# Rev1.net
KiCad netlist of a schematic drawn in EAGLE
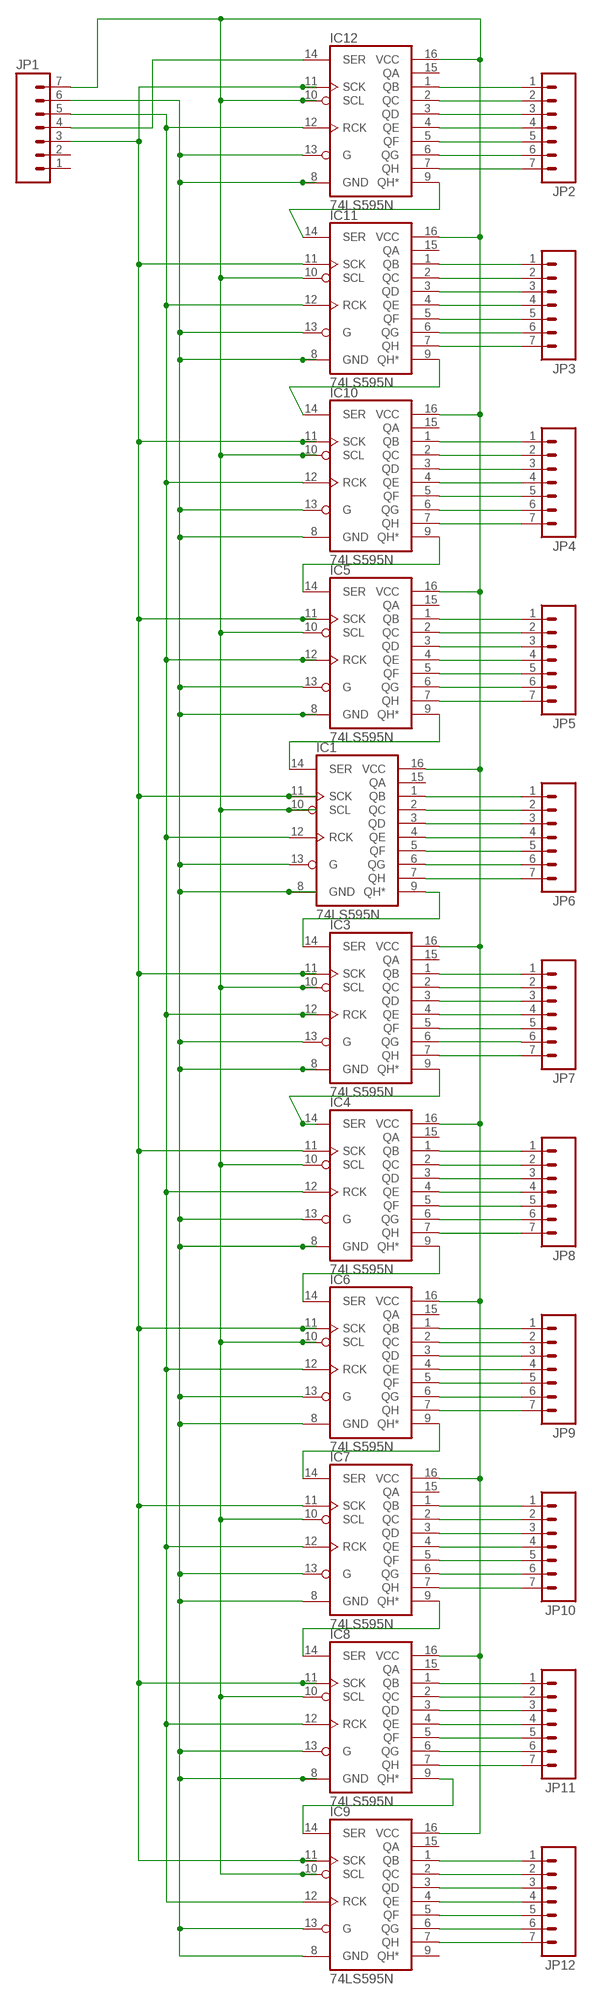
[diagram p0: schematic, sheet 1]

(export (version "E")
  (design (tool "Eeschema 10.0.6"))
  (components
    (comp (ref "IC1")
      (value "74LS595N")
      (footprint "eagle-import:DIL16")
      (libsource (lib "eagle-import") (part "74595NLS"))
    )
    (comp (ref "IC3")
      (value "74LS595N")
      (footprint "eagle-import:DIL16")
      (libsource (lib "eagle-import") (part "74595NLS"))
    )
    (comp (ref "IC4")
      (value "74LS595N")
      (footprint "eagle-import:DIL16")
      (libsource (lib "eagle-import") (part "74595NLS"))
    )
    (comp (ref "IC5")
      (value "74LS595N")
      (footprint "eagle-import:DIL16")
      (libsource (lib "eagle-import") (part "74595NLS"))
    )
    (comp (ref "IC6")
      (value "74LS595N")
      (footprint "eagle-import:DIL16")
      (libsource (lib "eagle-import") (part "74595NLS"))
    )
    (comp (ref "IC7")
      (value "74LS595N")
      (footprint "eagle-import:DIL16")
      (libsource (lib "eagle-import") (part "74595NLS"))
    )
    (comp (ref "IC8")
      (value "74LS595N")
      (footprint "eagle-import:DIL16")
      (libsource (lib "eagle-import") (part "74595NLS"))
    )
    (comp (ref "IC9")
      (value "74LS595N")
      (footprint "eagle-import:DIL16")
      (libsource (lib "eagle-import") (part "74595NLS"))
    )
    (comp (ref "IC10")
      (value "74LS595N")
      (footprint "eagle-import:DIL16")
      (libsource (lib "eagle-import") (part "74595NLS"))
    )
    (comp (ref "IC11")
      (value "74LS595N")
      (footprint "eagle-import:DIL16")
      (libsource (lib "eagle-import") (part "74595NLS"))
    )
    (comp (ref "IC12")
      (value "74LS595N")
      (footprint "eagle-import:DIL16")
      (libsource (lib "eagle-import") (part "74595NLS"))
    )
    (comp (ref "JP1")
      (value "M07")
      (footprint "eagle-import:1X07")
      (libsource (lib "eagle-import") (part "M07"))
    )
    (comp (ref "JP2")
      (value "M07")
      (footprint "eagle-import:1X07")
      (libsource (lib "eagle-import") (part "M07"))
    )
    (comp (ref "JP3")
      (value "M07")
      (footprint "eagle-import:1X07")
      (libsource (lib "eagle-import") (part "M07"))
    )
    (comp (ref "JP4")
      (value "M07")
      (footprint "eagle-import:1X07")
      (libsource (lib "eagle-import") (part "M07"))
    )
    (comp (ref "JP5")
      (value "M07")
      (footprint "eagle-import:1X07")
      (libsource (lib "eagle-import") (part "M07"))
    )
    (comp (ref "JP6")
      (value "M07")
      (footprint "eagle-import:1X07")
      (libsource (lib "eagle-import") (part "M07"))
    )
    (comp (ref "JP7")
      (value "M07")
      (footprint "eagle-import:1X07")
      (libsource (lib "eagle-import") (part "M07"))
    )
    (comp (ref "JP8")
      (value "M07")
      (footprint "eagle-import:1X07")
      (libsource (lib "eagle-import") (part "M07"))
    )
    (comp (ref "JP9")
      (value "M07")
      (footprint "eagle-import:1X07")
      (libsource (lib "eagle-import") (part "M07"))
    )
    (comp (ref "JP10")
      (value "M07")
      (footprint "eagle-import:1X07")
      (libsource (lib "eagle-import") (part "M07"))
    )
    (comp (ref "JP11")
      (value "M07")
      (footprint "eagle-import:1X07")
      (libsource (lib "eagle-import") (part "M07"))
    )
    (comp (ref "JP12")
      (value "M07")
      (footprint "eagle-import:1X07")
      (libsource (lib "eagle-import") (part "M07"))
    )
  )
  (nets
    (net (code "1") (name "Net-(IC1-G)") (class "Default")
      (node (ref "IC1") (pin "13") (pinfunction "G_13") (pintype "input"))
      (node (ref "IC1") (pin "8") (pinfunction "GND_8") (pintype "power_in"))
      (node (ref "IC10") (pin "13") (pinfunction "G_13") (pintype "input"))
      (node (ref "IC10") (pin "8") (pinfunction "GND_8") (pintype "power_in"))
      (node (ref "IC11") (pin "13") (pinfunction "G_13") (pintype "input"))
      (node (ref "IC11") (pin "8") (pinfunction "GND_8") (pintype "power_in"))
      (node (ref "IC12") (pin "13") (pinfunction "G_13") (pintype "input"))
      (node (ref "IC12") (pin "8") (pinfunction "GND_8") (pintype "power_in"))
      (node (ref "IC3") (pin "13") (pinfunction "G_13") (pintype "input"))
      (node (ref "IC3") (pin "8") (pinfunction "GND_8") (pintype "power_in"))
      (node (ref "IC4") (pin "13") (pinfunction "G_13") (pintype "input"))
      (node (ref "IC4") (pin "8") (pinfunction "GND_8") (pintype "power_in"))
      (node (ref "IC5") (pin "13") (pinfunction "G_13") (pintype "input"))
      (node (ref "IC5") (pin "8") (pinfunction "GND_8") (pintype "power_in"))
      (node (ref "IC6") (pin "13") (pinfunction "G_13") (pintype "input"))
      (node (ref "IC6") (pin "8") (pinfunction "GND_8") (pintype "power_in"))
      (node (ref "IC7") (pin "13") (pinfunction "G_13") (pintype "input"))
      (node (ref "IC7") (pin "8") (pinfunction "GND_8") (pintype "power_in"))
      (node (ref "IC8") (pin "13") (pinfunction "G_13") (pintype "input"))
      (node (ref "IC8") (pin "8") (pinfunction "GND_8") (pintype "power_in"))
      (node (ref "IC9") (pin "13") (pinfunction "G_13") (pintype "input"))
      (node (ref "IC9") (pin "8") (pinfunction "GND_8") (pintype "power_in"))
      (node (ref "JP1") (pin "6") (pinfunction "6_6") (pintype "passive"))
    )
    (net (code "2") (name "Net-(IC1-QB)") (class "Default")
      (node (ref "IC1") (pin "1") (pinfunction "QB_1") (pintype "tri_state"))
      (node (ref "JP6") (pin "1") (pinfunction "1_1") (pintype "passive"))
    )
    (net (code "3") (name "Net-(IC1-QC)") (class "Default")
      (node (ref "IC1") (pin "2") (pinfunction "QC_2") (pintype "tri_state"))
      (node (ref "JP6") (pin "2") (pinfunction "2_2") (pintype "passive"))
    )
    (net (code "4") (name "Net-(IC1-QD)") (class "Default")
      (node (ref "IC1") (pin "3") (pinfunction "QD_3") (pintype "tri_state"))
      (node (ref "JP6") (pin "3") (pinfunction "3_3") (pintype "passive"))
    )
    (net (code "5") (name "Net-(IC1-QE)") (class "Default")
      (node (ref "IC1") (pin "4") (pinfunction "QE_4") (pintype "tri_state"))
      (node (ref "JP6") (pin "4") (pinfunction "4_4") (pintype "passive"))
    )
    (net (code "6") (name "Net-(IC1-QF)") (class "Default")
      (node (ref "IC1") (pin "5") (pinfunction "QF_5") (pintype "tri_state"))
      (node (ref "JP6") (pin "5") (pinfunction "5_5") (pintype "passive"))
    )
    (net (code "7") (name "Net-(IC1-QG)") (class "Default")
      (node (ref "IC1") (pin "6") (pinfunction "QG_6") (pintype "tri_state"))
      (node (ref "JP6") (pin "6") (pinfunction "6_6") (pintype "passive"))
    )
    (net (code "8") (name "Net-(IC1-QH)") (class "Default")
      (node (ref "IC1") (pin "7") (pinfunction "QH_7") (pintype "tri_state"))
      (node (ref "JP6") (pin "7") (pinfunction "7_7") (pintype "passive"))
    )
    (net (code "9") (name "Net-(IC1-QH*)") (class "Default")
      (node (ref "IC1") (pin "9") (pinfunction "QH*_9") (pintype "tri_state"))
      (node (ref "IC3") (pin "14") (pinfunction "SER_14") (pintype "input"))
    )
    (net (code "10") (name "Net-(IC1-RCK)") (class "Default")
      (node (ref "IC1") (pin "12") (pinfunction "RCK_12") (pintype "input"))
      (node (ref "IC10") (pin "12") (pinfunction "RCK_12") (pintype "input"))
      (node (ref "IC11") (pin "12") (pinfunction "RCK_12") (pintype "input"))
      (node (ref "IC12") (pin "12") (pinfunction "RCK_12") (pintype "input"))
      (node (ref "IC3") (pin "12") (pinfunction "RCK_12") (pintype "input"))
      (node (ref "IC4") (pin "12") (pinfunction "RCK_12") (pintype "input"))
      (node (ref "IC5") (pin "12") (pinfunction "RCK_12") (pintype "input"))
      (node (ref "IC6") (pin "12") (pinfunction "RCK_12") (pintype "input"))
      (node (ref "IC7") (pin "12") (pinfunction "RCK_12") (pintype "input"))
      (node (ref "IC8") (pin "12") (pinfunction "RCK_12") (pintype "input"))
      (node (ref "IC9") (pin "12") (pinfunction "RCK_12") (pintype "input"))
      (node (ref "JP1") (pin "5") (pinfunction "5_5") (pintype "passive"))
    )
    (net (code "11") (name "Net-(IC1-SCK)") (class "Default")
      (node (ref "IC1") (pin "11") (pinfunction "SCK_11") (pintype "input"))
      (node (ref "IC10") (pin "11") (pinfunction "SCK_11") (pintype "input"))
      (node (ref "IC11") (pin "11") (pinfunction "SCK_11") (pintype "input"))
      (node (ref "IC12") (pin "11") (pinfunction "SCK_11") (pintype "input"))
      (node (ref "IC3") (pin "11") (pinfunction "SCK_11") (pintype "input"))
      (node (ref "IC4") (pin "11") (pinfunction "SCK_11") (pintype "input"))
      (node (ref "IC5") (pin "11") (pinfunction "SCK_11") (pintype "input"))
      (node (ref "IC6") (pin "11") (pinfunction "SCK_11") (pintype "input"))
      (node (ref "IC7") (pin "11") (pinfunction "SCK_11") (pintype "input"))
      (node (ref "IC8") (pin "11") (pinfunction "SCK_11") (pintype "input"))
      (node (ref "IC9") (pin "11") (pinfunction "SCK_11") (pintype "input"))
      (node (ref "JP1") (pin "3") (pinfunction "3_3") (pintype "passive"))
    )
    (net (code "12") (name "Net-(IC1-SCL)") (class "Default")
      (node (ref "IC1") (pin "10") (pinfunction "SCL_10") (pintype "input"))
      (node (ref "IC1") (pin "16") (pinfunction "VCC_16") (pintype "power_in"))
      (node (ref "IC10") (pin "10") (pinfunction "SCL_10") (pintype "input"))
      (node (ref "IC10") (pin "16") (pinfunction "VCC_16") (pintype "power_in"))
      (node (ref "IC11") (pin "10") (pinfunction "SCL_10") (pintype "input"))
      (node (ref "IC11") (pin "16") (pinfunction "VCC_16") (pintype "power_in"))
      (node (ref "IC12") (pin "10") (pinfunction "SCL_10") (pintype "input"))
      (node (ref "IC12") (pin "16") (pinfunction "VCC_16") (pintype "power_in"))
      (node (ref "IC3") (pin "10") (pinfunction "SCL_10") (pintype "input"))
      (node (ref "IC3") (pin "16") (pinfunction "VCC_16") (pintype "power_in"))
      (node (ref "IC4") (pin "10") (pinfunction "SCL_10") (pintype "input"))
      (node (ref "IC4") (pin "16") (pinfunction "VCC_16") (pintype "power_in"))
      (node (ref "IC5") (pin "10") (pinfunction "SCL_10") (pintype "input"))
      (node (ref "IC5") (pin "16") (pinfunction "VCC_16") (pintype "power_in"))
      (node (ref "IC6") (pin "10") (pinfunction "SCL_10") (pintype "input"))
      (node (ref "IC6") (pin "16") (pinfunction "VCC_16") (pintype "power_in"))
      (node (ref "IC7") (pin "10") (pinfunction "SCL_10") (pintype "input"))
      (node (ref "IC7") (pin "16") (pinfunction "VCC_16") (pintype "power_in"))
      (node (ref "IC8") (pin "10") (pinfunction "SCL_10") (pintype "input"))
      (node (ref "IC8") (pin "16") (pinfunction "VCC_16") (pintype "power_in"))
      (node (ref "IC9") (pin "10") (pinfunction "SCL_10") (pintype "input"))
      (node (ref "IC9") (pin "16") (pinfunction "VCC_16") (pintype "power_in"))
      (node (ref "JP1") (pin "7") (pinfunction "7_7") (pintype "passive"))
    )
    (net (code "13") (name "Net-(IC1-SER)") (class "Default")
      (node (ref "IC1") (pin "14") (pinfunction "SER_14") (pintype "input"))
      (node (ref "IC5") (pin "9") (pinfunction "QH*_9") (pintype "tri_state"))
    )
    (net (code "14") (name "Net-(IC3-QB)") (class "Default")
      (node (ref "IC3") (pin "1") (pinfunction "QB_1") (pintype "tri_state"))
      (node (ref "JP7") (pin "1") (pinfunction "1_1") (pintype "passive"))
    )
    (net (code "15") (name "Net-(IC3-QC)") (class "Default")
      (node (ref "IC3") (pin "2") (pinfunction "QC_2") (pintype "tri_state"))
      (node (ref "JP7") (pin "2") (pinfunction "2_2") (pintype "passive"))
    )
    (net (code "16") (name "Net-(IC3-QD)") (class "Default")
      (node (ref "IC3") (pin "3") (pinfunction "QD_3") (pintype "tri_state"))
      (node (ref "JP7") (pin "3") (pinfunction "3_3") (pintype "passive"))
    )
    (net (code "17") (name "Net-(IC3-QE)") (class "Default")
      (node (ref "IC3") (pin "4") (pinfunction "QE_4") (pintype "tri_state"))
      (node (ref "JP7") (pin "4") (pinfunction "4_4") (pintype "passive"))
    )
    (net (code "18") (name "Net-(IC3-QF)") (class "Default")
      (node (ref "IC3") (pin "5") (pinfunction "QF_5") (pintype "tri_state"))
      (node (ref "JP7") (pin "5") (pinfunction "5_5") (pintype "passive"))
    )
    (net (code "19") (name "Net-(IC3-QG)") (class "Default")
      (node (ref "IC3") (pin "6") (pinfunction "QG_6") (pintype "tri_state"))
      (node (ref "JP7") (pin "6") (pinfunction "6_6") (pintype "passive"))
    )
    (net (code "20") (name "Net-(IC3-QH)") (class "Default")
      (node (ref "IC3") (pin "7") (pinfunction "QH_7") (pintype "tri_state"))
      (node (ref "JP7") (pin "7") (pinfunction "7_7") (pintype "passive"))
    )
    (net (code "21") (name "Net-(IC3-QH*)") (class "Default")
      (node (ref "IC3") (pin "9") (pinfunction "QH*_9") (pintype "tri_state"))
      (node (ref "IC4") (pin "14") (pinfunction "SER_14") (pintype "input"))
    )
    (net (code "22") (name "Net-(IC4-QB)") (class "Default")
      (node (ref "IC4") (pin "1") (pinfunction "QB_1") (pintype "tri_state"))
      (node (ref "JP8") (pin "1") (pinfunction "1_1") (pintype "passive"))
    )
    (net (code "23") (name "Net-(IC4-QC)") (class "Default")
      (node (ref "IC4") (pin "2") (pinfunction "QC_2") (pintype "tri_state"))
      (node (ref "JP8") (pin "2") (pinfunction "2_2") (pintype "passive"))
    )
    (net (code "24") (name "Net-(IC4-QD)") (class "Default")
      (node (ref "IC4") (pin "3") (pinfunction "QD_3") (pintype "tri_state"))
      (node (ref "JP8") (pin "3") (pinfunction "3_3") (pintype "passive"))
    )
    (net (code "25") (name "Net-(IC4-QE)") (class "Default")
      (node (ref "IC4") (pin "4") (pinfunction "QE_4") (pintype "tri_state"))
      (node (ref "JP8") (pin "4") (pinfunction "4_4") (pintype "passive"))
    )
    (net (code "26") (name "Net-(IC4-QF)") (class "Default")
      (node (ref "IC4") (pin "5") (pinfunction "QF_5") (pintype "tri_state"))
      (node (ref "JP8") (pin "5") (pinfunction "5_5") (pintype "passive"))
    )
    (net (code "27") (name "Net-(IC4-QG)") (class "Default")
      (node (ref "IC4") (pin "6") (pinfunction "QG_6") (pintype "tri_state"))
      (node (ref "JP8") (pin "6") (pinfunction "6_6") (pintype "passive"))
    )
    (net (code "28") (name "Net-(IC4-QH)") (class "Default")
      (node (ref "IC4") (pin "7") (pinfunction "QH_7") (pintype "tri_state"))
      (node (ref "JP8") (pin "7") (pinfunction "7_7") (pintype "passive"))
    )
    (net (code "29") (name "Net-(IC4-QH*)") (class "Default")
      (node (ref "IC4") (pin "9") (pinfunction "QH*_9") (pintype "tri_state"))
      (node (ref "IC6") (pin "14") (pinfunction "SER_14") (pintype "input"))
    )
    (net (code "30") (name "Net-(IC5-QB)") (class "Default")
      (node (ref "IC5") (pin "1") (pinfunction "QB_1") (pintype "tri_state"))
      (node (ref "JP5") (pin "1") (pinfunction "1_1") (pintype "passive"))
    )
    (net (code "31") (name "Net-(IC5-QC)") (class "Default")
      (node (ref "IC5") (pin "2") (pinfunction "QC_2") (pintype "tri_state"))
      (node (ref "JP5") (pin "2") (pinfunction "2_2") (pintype "passive"))
    )
    (net (code "32") (name "Net-(IC5-QD)") (class "Default")
      (node (ref "IC5") (pin "3") (pinfunction "QD_3") (pintype "tri_state"))
      (node (ref "JP5") (pin "3") (pinfunction "3_3") (pintype "passive"))
    )
    (net (code "33") (name "Net-(IC5-QE)") (class "Default")
      (node (ref "IC5") (pin "4") (pinfunction "QE_4") (pintype "tri_state"))
      (node (ref "JP5") (pin "4") (pinfunction "4_4") (pintype "passive"))
    )
    (net (code "34") (name "Net-(IC5-QF)") (class "Default")
      (node (ref "IC5") (pin "5") (pinfunction "QF_5") (pintype "tri_state"))
      (node (ref "JP5") (pin "5") (pinfunction "5_5") (pintype "passive"))
    )
    (net (code "35") (name "Net-(IC5-QG)") (class "Default")
      (node (ref "IC5") (pin "6") (pinfunction "QG_6") (pintype "tri_state"))
      (node (ref "JP5") (pin "6") (pinfunction "6_6") (pintype "passive"))
    )
    (net (code "36") (name "Net-(IC5-QH)") (class "Default")
      (node (ref "IC5") (pin "7") (pinfunction "QH_7") (pintype "tri_state"))
      (node (ref "JP5") (pin "7") (pinfunction "7_7") (pintype "passive"))
    )
    (net (code "37") (name "Net-(IC6-QB)") (class "Default")
      (node (ref "IC6") (pin "1") (pinfunction "QB_1") (pintype "tri_state"))
      (node (ref "JP9") (pin "1") (pinfunction "1_1") (pintype "passive"))
    )
    (net (code "38") (name "Net-(IC6-QC)") (class "Default")
      (node (ref "IC6") (pin "2") (pinfunction "QC_2") (pintype "tri_state"))
      (node (ref "JP9") (pin "2") (pinfunction "2_2") (pintype "passive"))
    )
    (net (code "39") (name "Net-(IC6-QD)") (class "Default")
      (node (ref "IC6") (pin "3") (pinfunction "QD_3") (pintype "tri_state"))
      (node (ref "JP9") (pin "3") (pinfunction "3_3") (pintype "passive"))
    )
    (net (code "40") (name "Net-(IC6-QE)") (class "Default")
      (node (ref "IC6") (pin "4") (pinfunction "QE_4") (pintype "tri_state"))
      (node (ref "JP9") (pin "4") (pinfunction "4_4") (pintype "passive"))
    )
    (net (code "41") (name "Net-(IC6-QF)") (class "Default")
      (node (ref "IC6") (pin "5") (pinfunction "QF_5") (pintype "tri_state"))
      (node (ref "JP9") (pin "5") (pinfunction "5_5") (pintype "passive"))
    )
    (net (code "42") (name "Net-(IC6-QG)") (class "Default")
      (node (ref "IC6") (pin "6") (pinfunction "QG_6") (pintype "tri_state"))
      (node (ref "JP9") (pin "6") (pinfunction "6_6") (pintype "passive"))
    )
    (net (code "43") (name "Net-(IC6-QH)") (class "Default")
      (node (ref "IC6") (pin "7") (pinfunction "QH_7") (pintype "tri_state"))
      (node (ref "JP9") (pin "7") (pinfunction "7_7") (pintype "passive"))
    )
    (net (code "44") (name "Net-(IC6-QH*)") (class "Default")
      (node (ref "IC6") (pin "9") (pinfunction "QH*_9") (pintype "tri_state"))
      (node (ref "IC7") (pin "14") (pinfunction "SER_14") (pintype "input"))
    )
    (net (code "45") (name "Net-(IC7-QB)") (class "Default")
      (node (ref "IC7") (pin "1") (pinfunction "QB_1") (pintype "tri_state"))
      (node (ref "JP10") (pin "1") (pinfunction "1_1") (pintype "passive"))
    )
    (net (code "46") (name "Net-(IC7-QC)") (class "Default")
      (node (ref "IC7") (pin "2") (pinfunction "QC_2") (pintype "tri_state"))
      (node (ref "JP10") (pin "2") (pinfunction "2_2") (pintype "passive"))
    )
    (net (code "47") (name "Net-(IC7-QD)") (class "Default")
      (node (ref "IC7") (pin "3") (pinfunction "QD_3") (pintype "tri_state"))
      (node (ref "JP10") (pin "3") (pinfunction "3_3") (pintype "passive"))
    )
    (net (code "48") (name "Net-(IC7-QE)") (class "Default")
      (node (ref "IC7") (pin "4") (pinfunction "QE_4") (pintype "tri_state"))
      (node (ref "JP10") (pin "4") (pinfunction "4_4") (pintype "passive"))
    )
    (net (code "49") (name "Net-(IC7-QF)") (class "Default")
      (node (ref "IC7") (pin "5") (pinfunction "QF_5") (pintype "tri_state"))
      (node (ref "JP10") (pin "5") (pinfunction "5_5") (pintype "passive"))
    )
    (net (code "50") (name "Net-(IC7-QG)") (class "Default")
      (node (ref "IC7") (pin "6") (pinfunction "QG_6") (pintype "tri_state"))
      (node (ref "JP10") (pin "6") (pinfunction "6_6") (pintype "passive"))
    )
    (net (code "51") (name "Net-(IC7-QH)") (class "Default")
      (node (ref "IC7") (pin "7") (pinfunction "QH_7") (pintype "tri_state"))
      (node (ref "JP10") (pin "7") (pinfunction "7_7") (pintype "passive"))
    )
    (net (code "52") (name "Net-(IC7-QH*)") (class "Default")
      (node (ref "IC7") (pin "9") (pinfunction "QH*_9") (pintype "tri_state"))
      (node (ref "IC8") (pin "14") (pinfunction "SER_14") (pintype "input"))
    )
    (net (code "53") (name "Net-(IC8-QB)") (class "Default")
      (node (ref "IC8") (pin "1") (pinfunction "QB_1") (pintype "tri_state"))
      (node (ref "JP11") (pin "1") (pinfunction "1_1") (pintype "passive"))
    )
    (net (code "54") (name "Net-(IC8-QC)") (class "Default")
      (node (ref "IC8") (pin "2") (pinfunction "QC_2") (pintype "tri_state"))
      (node (ref "JP11") (pin "2") (pinfunction "2_2") (pintype "passive"))
    )
    (net (code "55") (name "Net-(IC8-QD)") (class "Default")
      (node (ref "IC8") (pin "3") (pinfunction "QD_3") (pintype "tri_state"))
      (node (ref "JP11") (pin "3") (pinfunction "3_3") (pintype "passive"))
    )
    (net (code "56") (name "Net-(IC8-QE)") (class "Default")
      (node (ref "IC8") (pin "4") (pinfunction "QE_4") (pintype "tri_state"))
      (node (ref "JP11") (pin "4") (pinfunction "4_4") (pintype "passive"))
    )
    (net (code "57") (name "Net-(IC8-QF)") (class "Default")
      (node (ref "IC8") (pin "5") (pinfunction "QF_5") (pintype "tri_state"))
      (node (ref "JP11") (pin "5") (pinfunction "5_5") (pintype "passive"))
    )
    (net (code "58") (name "Net-(IC8-QG)") (class "Default")
      (node (ref "IC8") (pin "6") (pinfunction "QG_6") (pintype "tri_state"))
      (node (ref "JP11") (pin "6") (pinfunction "6_6") (pintype "passive"))
    )
    (net (code "59") (name "Net-(IC8-QH)") (class "Default")
      (node (ref "IC8") (pin "7") (pinfunction "QH_7") (pintype "tri_state"))
      (node (ref "JP11") (pin "7") (pinfunction "7_7") (pintype "passive"))
    )
    (net (code "60") (name "Net-(IC8-QH*)") (class "Default")
      (node (ref "IC8") (pin "9") (pinfunction "QH*_9") (pintype "tri_state"))
      (node (ref "IC9") (pin "14") (pinfunction "SER_14") (pintype "input"))
    )
    (net (code "61") (name "Net-(IC9-QB)") (class "Default")
      (node (ref "IC9") (pin "1") (pinfunction "QB_1") (pintype "tri_state"))
      (node (ref "JP12") (pin "1") (pinfunction "1_1") (pintype "passive"))
    )
    (net (code "62") (name "Net-(IC9-QC)") (class "Default")
      (node (ref "IC9") (pin "2") (pinfunction "QC_2") (pintype "tri_state"))
      (node (ref "JP12") (pin "2") (pinfunction "2_2") (pintype "passive"))
    )
    (net (code "63") (name "Net-(IC9-QD)") (class "Default")
      (node (ref "IC9") (pin "3") (pinfunction "QD_3") (pintype "tri_state"))
      (node (ref "JP12") (pin "3") (pinfunction "3_3") (pintype "passive"))
    )
    (net (code "64") (name "Net-(IC9-QE)") (class "Default")
      (node (ref "IC9") (pin "4") (pinfunction "QE_4") (pintype "tri_state"))
      (node (ref "JP12") (pin "4") (pinfunction "4_4") (pintype "passive"))
    )
    (net (code "65") (name "Net-(IC9-QF)") (class "Default")
      (node (ref "IC9") (pin "5") (pinfunction "QF_5") (pintype "tri_state"))
      (node (ref "JP12") (pin "5") (pinfunction "5_5") (pintype "passive"))
    )
    (net (code "66") (name "Net-(IC9-QG)") (class "Default")
      (node (ref "IC9") (pin "6") (pinfunction "QG_6") (pintype "tri_state"))
      (node (ref "JP12") (pin "6") (pinfunction "6_6") (pintype "passive"))
    )
    (net (code "67") (name "Net-(IC9-QH)") (class "Default")
      (node (ref "IC9") (pin "7") (pinfunction "QH_7") (pintype "tri_state"))
      (node (ref "JP12") (pin "7") (pinfunction "7_7") (pintype "passive"))
    )
    (net (code "68") (name "Net-(IC10-QB)") (class "Default")
      (node (ref "IC10") (pin "1") (pinfunction "QB_1") (pintype "tri_state"))
      (node (ref "JP4") (pin "1") (pinfunction "1_1") (pintype "passive"))
    )
    (net (code "69") (name "Net-(IC10-QC)") (class "Default")
      (node (ref "IC10") (pin "2") (pinfunction "QC_2") (pintype "tri_state"))
      (node (ref "JP4") (pin "2") (pinfunction "2_2") (pintype "passive"))
    )
    (net (code "70") (name "Net-(IC10-QD)") (class "Default")
      (node (ref "IC10") (pin "3") (pinfunction "QD_3") (pintype "tri_state"))
      (node (ref "JP4") (pin "3") (pinfunction "3_3") (pintype "passive"))
    )
    (net (code "71") (name "Net-(IC10-QE)") (class "Default")
      (node (ref "IC10") (pin "4") (pinfunction "QE_4") (pintype "tri_state"))
      (node (ref "JP4") (pin "4") (pinfunction "4_4") (pintype "passive"))
    )
    (net (code "72") (name "Net-(IC10-QF)") (class "Default")
      (node (ref "IC10") (pin "5") (pinfunction "QF_5") (pintype "tri_state"))
      (node (ref "JP4") (pin "5") (pinfunction "5_5") (pintype "passive"))
    )
    (net (code "73") (name "Net-(IC10-QG)") (class "Default")
      (node (ref "IC10") (pin "6") (pinfunction "QG_6") (pintype "tri_state"))
      (node (ref "JP4") (pin "6") (pinfunction "6_6") (pintype "passive"))
    )
    (net (code "74") (name "Net-(IC10-QH)") (class "Default")
      (node (ref "IC10") (pin "7") (pinfunction "QH_7") (pintype "tri_state"))
      (node (ref "JP4") (pin "7") (pinfunction "7_7") (pintype "passive"))
    )
    (net (code "75") (name "Net-(IC10-QH*)") (class "Default")
      (node (ref "IC10") (pin "9") (pinfunction "QH*_9") (pintype "tri_state"))
      (node (ref "IC5") (pin "14") (pinfunction "SER_14") (pintype "input"))
    )
    (net (code "76") (name "Net-(IC10-SER)") (class "Default")
      (node (ref "IC10") (pin "14") (pinfunction "SER_14") (pintype "input"))
      (node (ref "IC11") (pin "9") (pinfunction "QH*_9") (pintype "tri_state"))
    )
    (net (code "77") (name "Net-(IC11-QB)") (class "Default")
      (node (ref "IC11") (pin "1") (pinfunction "QB_1") (pintype "tri_state"))
      (node (ref "JP3") (pin "1") (pinfunction "1_1") (pintype "passive"))
    )
    (net (code "78") (name "Net-(IC11-QC)") (class "Default")
      (node (ref "IC11") (pin "2") (pinfunction "QC_2") (pintype "tri_state"))
      (node (ref "JP3") (pin "2") (pinfunction "2_2") (pintype "passive"))
    )
    (net (code "79") (name "Net-(IC11-QD)") (class "Default")
      (node (ref "IC11") (pin "3") (pinfunction "QD_3") (pintype "tri_state"))
      (node (ref "JP3") (pin "3") (pinfunction "3_3") (pintype "passive"))
    )
    (net (code "80") (name "Net-(IC11-QE)") (class "Default")
      (node (ref "IC11") (pin "4") (pinfunction "QE_4") (pintype "tri_state"))
      (node (ref "JP3") (pin "4") (pinfunction "4_4") (pintype "passive"))
    )
    (net (code "81") (name "Net-(IC11-QF)") (class "Default")
      (node (ref "IC11") (pin "5") (pinfunction "QF_5") (pintype "tri_state"))
      (node (ref "JP3") (pin "5") (pinfunction "5_5") (pintype "passive"))
    )
    (net (code "82") (name "Net-(IC11-QG)") (class "Default")
      (node (ref "IC11") (pin "6") (pinfunction "QG_6") (pintype "tri_state"))
      (node (ref "JP3") (pin "6") (pinfunction "6_6") (pintype "passive"))
    )
    (net (code "83") (name "Net-(IC11-QH)") (class "Default")
      (node (ref "IC11") (pin "7") (pinfunction "QH_7") (pintype "tri_state"))
      (node (ref "JP3") (pin "7") (pinfunction "7_7") (pintype "passive"))
    )
    (net (code "84") (name "Net-(IC11-SER)") (class "Default")
      (node (ref "IC11") (pin "14") (pinfunction "SER_14") (pintype "input"))
      (node (ref "IC12") (pin "9") (pinfunction "QH*_9") (pintype "tri_state"))
    )
    (net (code "85") (name "Net-(IC12-QB)") (class "Default")
      (node (ref "IC12") (pin "1") (pinfunction "QB_1") (pintype "tri_state"))
      (node (ref "JP2") (pin "1") (pinfunction "1_1") (pintype "passive"))
    )
    (net (code "86") (name "Net-(IC12-QC)") (class "Default")
      (node (ref "IC12") (pin "2") (pinfunction "QC_2") (pintype "tri_state"))
      (node (ref "JP2") (pin "2") (pinfunction "2_2") (pintype "passive"))
    )
    (net (code "87") (name "Net-(IC12-QD)") (class "Default")
      (node (ref "IC12") (pin "3") (pinfunction "QD_3") (pintype "tri_state"))
      (node (ref "JP2") (pin "3") (pinfunction "3_3") (pintype "passive"))
    )
    (net (code "88") (name "Net-(IC12-QE)") (class "Default")
      (node (ref "IC12") (pin "4") (pinfunction "QE_4") (pintype "tri_state"))
      (node (ref "JP2") (pin "4") (pinfunction "4_4") (pintype "passive"))
    )
    (net (code "89") (name "Net-(IC12-QF)") (class "Default")
      (node (ref "IC12") (pin "5") (pinfunction "QF_5") (pintype "tri_state"))
      (node (ref "JP2") (pin "5") (pinfunction "5_5") (pintype "passive"))
    )
    (net (code "90") (name "Net-(IC12-QG)") (class "Default")
      (node (ref "IC12") (pin "6") (pinfunction "QG_6") (pintype "tri_state"))
      (node (ref "JP2") (pin "6") (pinfunction "6_6") (pintype "passive"))
    )
    (net (code "91") (name "Net-(IC12-QH)") (class "Default")
      (node (ref "IC12") (pin "7") (pinfunction "QH_7") (pintype "tri_state"))
      (node (ref "JP2") (pin "7") (pinfunction "7_7") (pintype "passive"))
    )
    (net (code "92") (name "Net-(IC12-SER)") (class "Default")
      (node (ref "IC12") (pin "14") (pinfunction "SER_14") (pintype "input"))
      (node (ref "JP1") (pin "4") (pinfunction "4_4") (pintype "passive"))
    )
    (net (code "93") (name "unconnected-(IC1-QA-Pad15)") (class "Default")
      (node (ref "IC1") (pin "15") (pinfunction "QA_15") (pintype "tri_state"))
    )
    (net (code "94") (name "unconnected-(IC3-QA-Pad15)") (class "Default")
      (node (ref "IC3") (pin "15") (pinfunction "QA_15") (pintype "tri_state"))
    )
    (net (code "95") (name "unconnected-(IC4-QA-Pad15)") (class "Default")
      (node (ref "IC4") (pin "15") (pinfunction "QA_15") (pintype "tri_state"))
    )
    (net (code "96") (name "unconnected-(IC5-QA-Pad15)") (class "Default")
      (node (ref "IC5") (pin "15") (pinfunction "QA_15") (pintype "tri_state"))
    )
    (net (code "97") (name "unconnected-(IC6-QA-Pad15)") (class "Default")
      (node (ref "IC6") (pin "15") (pinfunction "QA_15") (pintype "tri_state"))
    )
    (net (code "98") (name "unconnected-(IC7-QA-Pad15)") (class "Default")
      (node (ref "IC7") (pin "15") (pinfunction "QA_15") (pintype "tri_state"))
    )
    (net (code "99") (name "unconnected-(IC8-QA-Pad15)") (class "Default")
      (node (ref "IC8") (pin "15") (pinfunction "QA_15") (pintype "tri_state"))
    )
    (net (code "100") (name "unconnected-(IC9-QA-Pad15)") (class "Default")
      (node (ref "IC9") (pin "15") (pinfunction "QA_15") (pintype "tri_state"))
    )
    (net (code "101") (name "unconnected-(IC9-QH*-Pad9)") (class "Default")
      (node (ref "IC9") (pin "9") (pinfunction "QH*_9") (pintype "tri_state"))
    )
    (net (code "102") (name "unconnected-(IC10-QA-Pad15)") (class "Default")
      (node (ref "IC10") (pin "15") (pinfunction "QA_15") (pintype "tri_state"))
    )
    (net (code "103") (name "unconnected-(IC11-QA-Pad15)") (class "Default")
      (node (ref "IC11") (pin "15") (pinfunction "QA_15") (pintype "tri_state"))
    )
    (net (code "104") (name "unconnected-(IC12-QA-Pad15)") (class "Default")
      (node (ref "IC12") (pin "15") (pinfunction "QA_15") (pintype "tri_state"))
    )
    (net (code "105") (name "unconnected-(JP1-Pad1)") (class "Default")
      (node (ref "JP1") (pin "1") (pinfunction "1_1") (pintype "passive"))
    )
    (net (code "106") (name "unconnected-(JP1-Pad2)") (class "Default")
      (node (ref "JP1") (pin "2") (pinfunction "2_2") (pintype "passive"))
    )
  )
)
